# stackclock_base.net
KiCad netlist of a schematic drawn in EAGLE
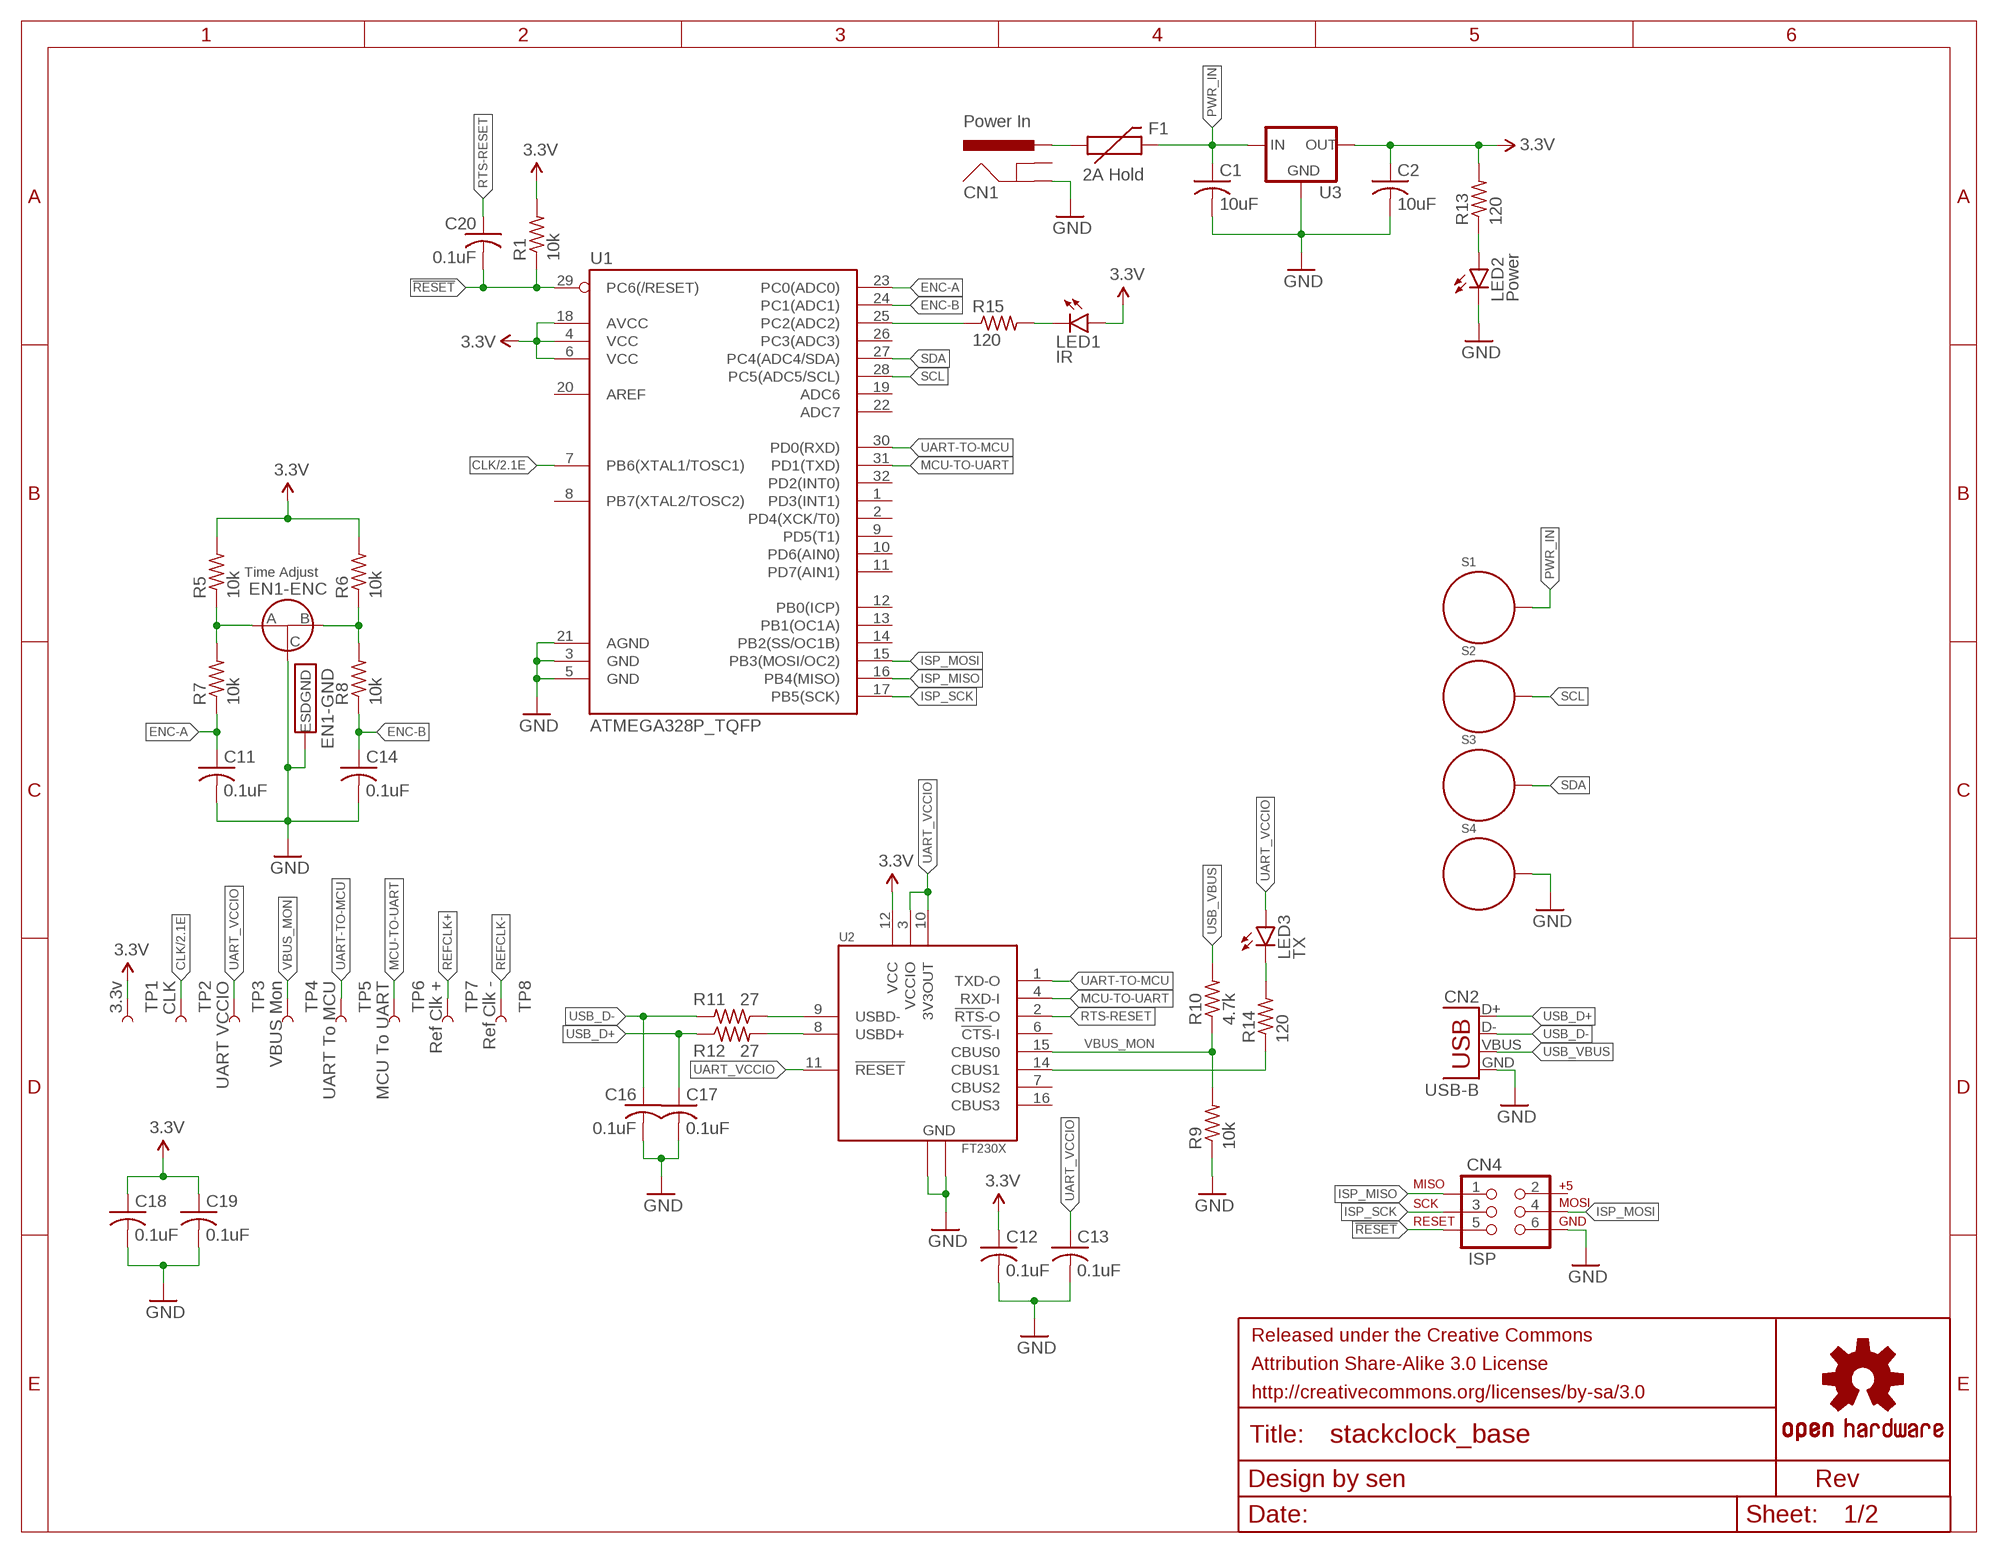
[diagram p0: schematic, sheet 1]
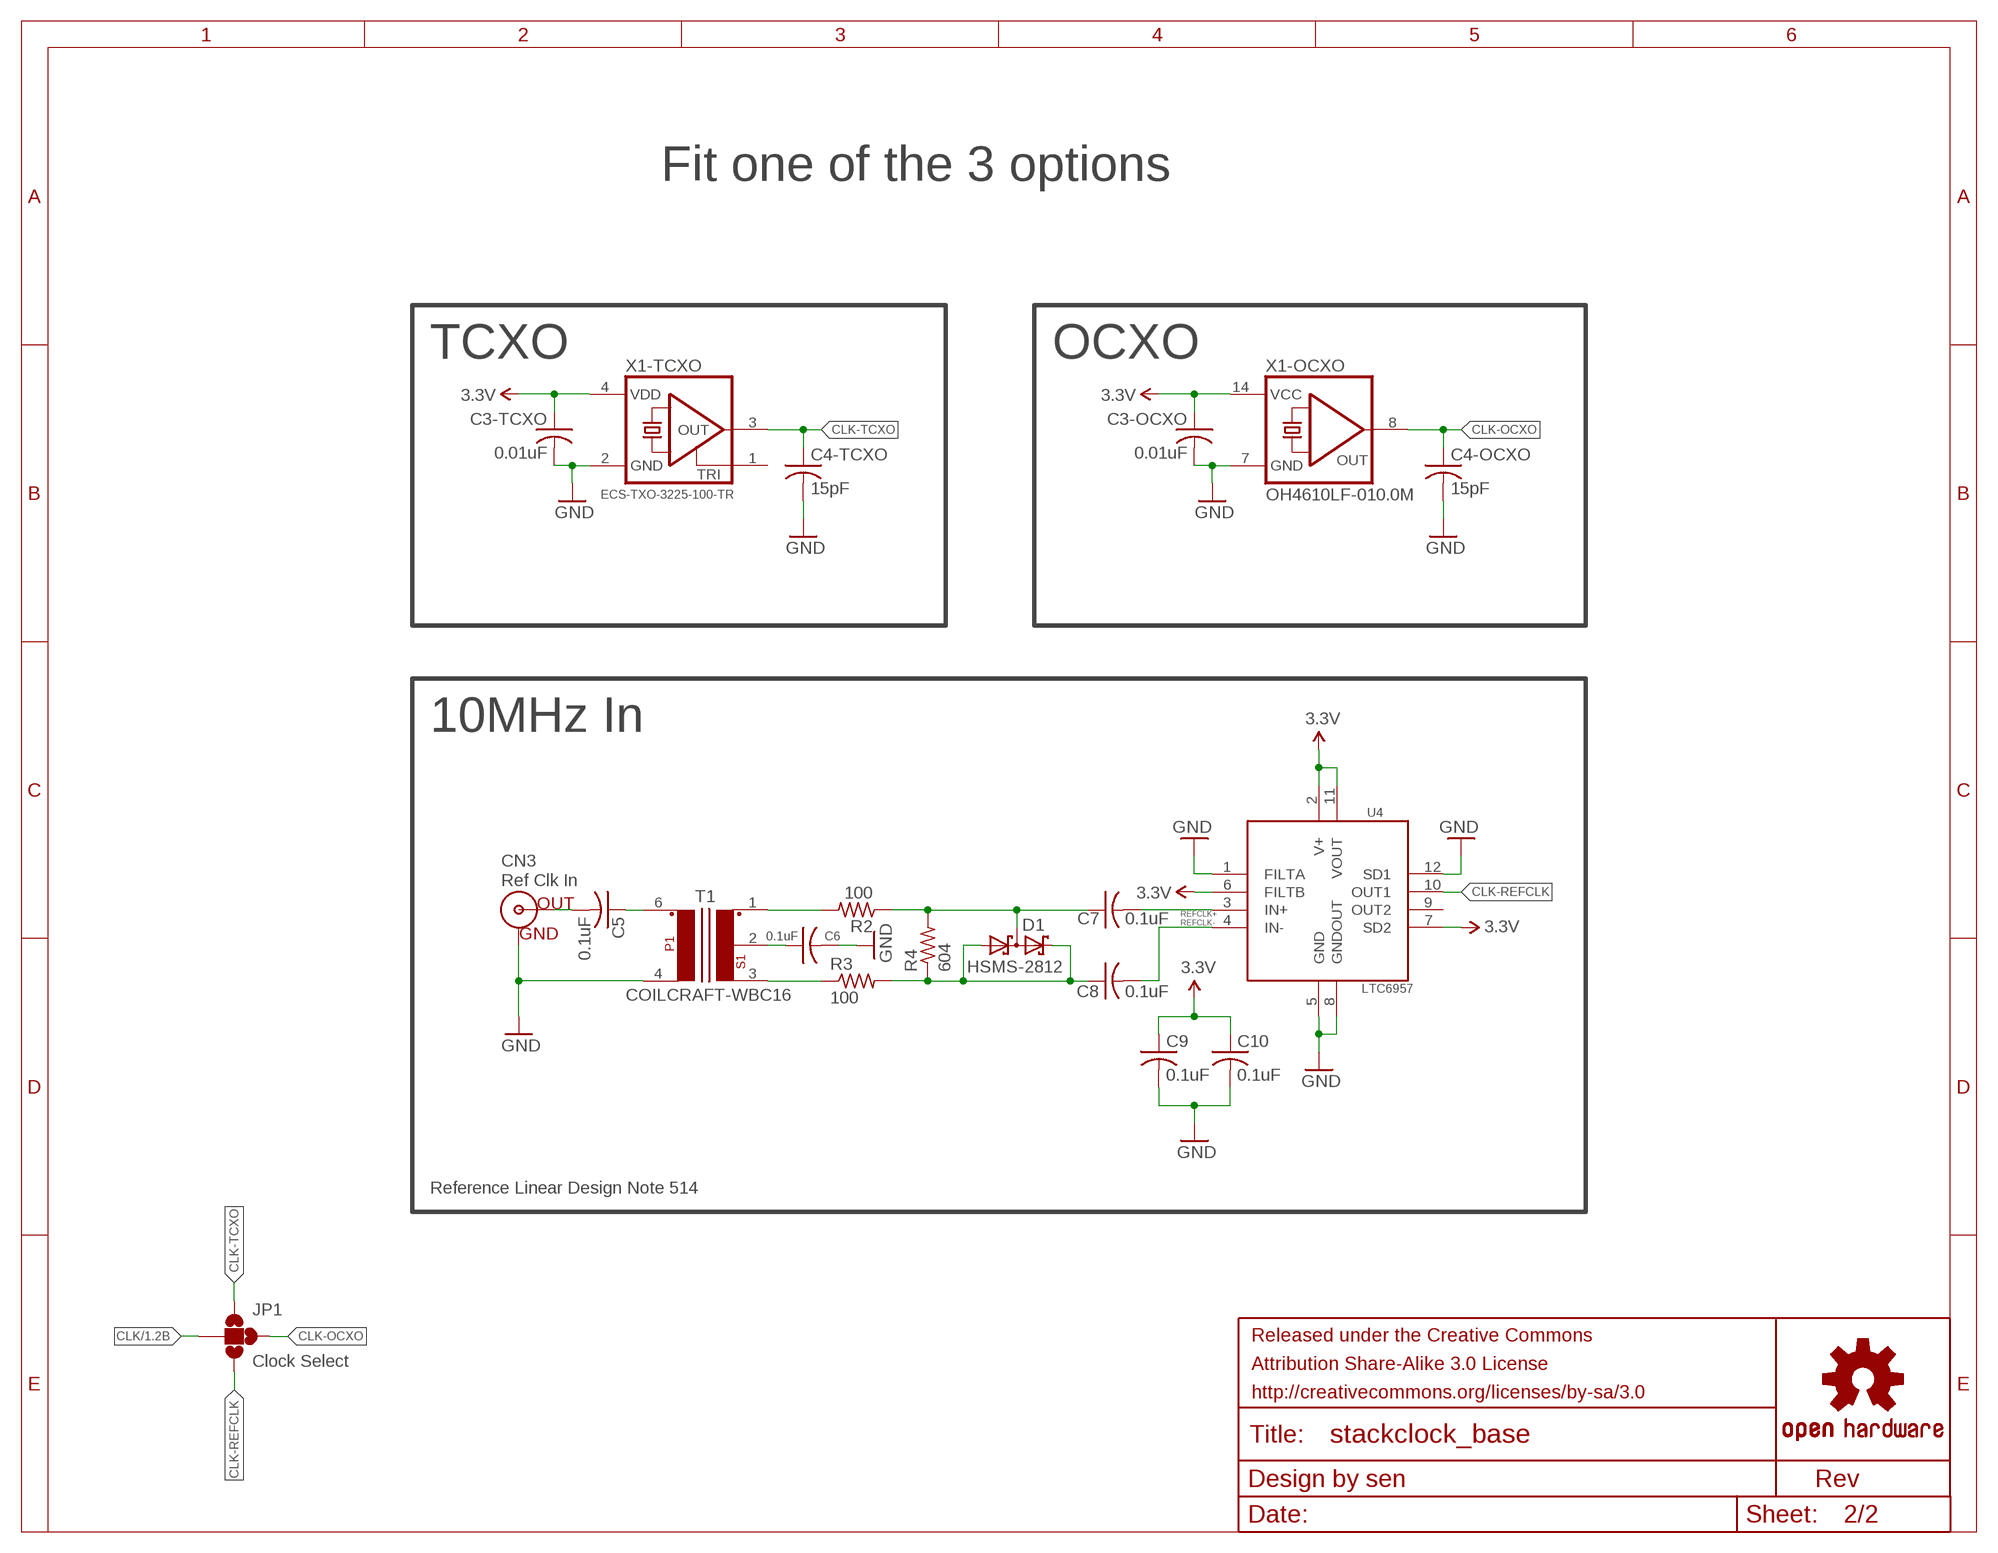
[diagram p1: schematic, sheet 2]

(export (version "E")
  (design (tool "Eeschema 10.0.6"))
  (components
    (comp (ref "C3-OCXO")
      (value "0.01uF")
      (footprint "eagle-import:C0603")
      (libsource (lib "eagle-import") (part "C-USC0603"))
    )
    (comp (ref "C3-TCXO")
      (value "0.01uF")
      (footprint "eagle-import:C0603")
      (libsource (lib "eagle-import") (part "C-USC0603"))
    )
    (comp (ref "C4-OCXO")
      (value "15pF")
      (footprint "eagle-import:C0603")
      (libsource (lib "eagle-import") (part "C-USC0603"))
    )
    (comp (ref "C4-TCXO")
      (value "15pF")
      (footprint "eagle-import:C0603")
      (libsource (lib "eagle-import") (part "C-USC0603"))
    )
    (comp (ref "C5")
      (value "0.1uF")
      (footprint "eagle-import:C0603")
      (libsource (lib "eagle-import") (part "C-USC0603"))
    )
    (comp (ref "C6")
      (value "0.1uF")
      (footprint "eagle-import:C0603")
      (libsource (lib "eagle-import") (part "C-USC0603"))
    )
    (comp (ref "C7")
      (value "0.1uF")
      (footprint "eagle-import:C0603")
      (libsource (lib "eagle-import") (part "C-USC0603"))
    )
    (comp (ref "C8")
      (value "0.1uF")
      (footprint "eagle-import:C0603")
      (libsource (lib "eagle-import") (part "C-USC0603"))
    )
    (comp (ref "C9")
      (value "0.1uF")
      (footprint "eagle-import:C0603")
      (libsource (lib "eagle-import") (part "C-USC0603"))
    )
    (comp (ref "C10")
      (value "0.1uF")
      (footprint "eagle-import:C0603")
      (libsource (lib "eagle-import") (part "C-USC0603"))
    )
    (comp (ref "CN3")
      (value "Ref Clk In")
      (footprint "eagle-import:BNC")
      (libsource (lib "eagle-import") (part "BNCPTH"))
    )
    (comp (ref "D1")
      (value "HSMS-2812")
      (footprint "eagle-import:SOT23")
      (libsource (lib "eagle-import") (part "BAT54S"))
    )
    (comp (ref "FRAME2")
      (value "FRAME-LETTER-GRID-OSHW-SENOSHW-LOGO-L")
      (footprint "eagle-import:OSHW-LOGO-L")
      (fields (field (name "REV") "001"))
      (libsource (lib "eagle-import") (part "FRAME-LETTER-GRID-OSHW-SENOSHW-LOGO-L"))
    )
    (comp (ref "JP1")
      (value "Clock Select")
      (footprint "eagle-import:PAD-JUMPER-4-NO_YES_SILK")
      (libsource (lib "eagle-import") (part "JUMPER-PAD-4-NOYES_SILK"))
    )
    (comp (ref "R2")
      (value "100")
      (footprint "eagle-import:R0603")
      (libsource (lib "eagle-import") (part "R-US_R0603"))
    )
    (comp (ref "R3")
      (value "100")
      (footprint "eagle-import:R0603")
      (libsource (lib "eagle-import") (part "R-US_R0603"))
    )
    (comp (ref "R4")
      (value "604")
      (footprint "eagle-import:R0603")
      (libsource (lib "eagle-import") (part "R-US_R0603"))
    )
    (comp (ref "T1")
      (value "COILCRAFT-WBC16")
      (footprint "eagle-import:COILCRAFT-WBC")
      (libsource (lib "eagle-import") (part "COILCRAFT-WBC16-1TL"))
    )
    (comp (ref "U4")
      (value "LTC6957")
      (footprint "eagle-import:MSOP12")
      (libsource (lib "eagle-import") (part "LTC6957"))
    )
    (comp (ref "X1-OCXO")
      (value "OH4610LF-010.0M")
      (footprint "eagle-import:DIL14S")
      (libsource (lib "eagle-import") (part "QG5860"))
    )
    (comp (ref "X1-TCXO")
      (value "ECS-TXO-3225-100-TR")
      (footprint "eagle-import:ASE")
      (libsource (lib "eagle-import") (part "ASE"))
    )
    (comp (ref "C1")
      (value "10uF")
      (footprint "eagle-import:C0805")
      (libsource (lib "eagle-import") (part "C-USC0805"))
    )
    (comp (ref "C2")
      (value "10uF")
      (footprint "eagle-import:C0805")
      (libsource (lib "eagle-import") (part "C-USC0805"))
    )
    (comp (ref "C11")
      (value "0.1uF")
      (footprint "eagle-import:C0603")
      (libsource (lib "eagle-import") (part "C-USC0603"))
    )
    (comp (ref "C12")
      (value "0.1uF")
      (footprint "eagle-import:C0603")
      (libsource (lib "eagle-import") (part "C-USC0603"))
    )
    (comp (ref "C13")
      (value "0.1uF")
      (footprint "eagle-import:C0603")
      (libsource (lib "eagle-import") (part "C-USC0603"))
    )
    (comp (ref "C14")
      (value "0.1uF")
      (footprint "eagle-import:C0603")
      (libsource (lib "eagle-import") (part "C-USC0603"))
    )
    (comp (ref "C16")
      (value "0.1uF")
      (footprint "eagle-import:C0603")
      (libsource (lib "eagle-import") (part "C-USC0603"))
    )
    (comp (ref "C17")
      (value "0.1uF")
      (footprint "eagle-import:C0603")
      (libsource (lib "eagle-import") (part "C-USC0603"))
    )
    (comp (ref "C18")
      (value "0.1uF")
      (footprint "eagle-import:C0603")
      (libsource (lib "eagle-import") (part "C-USC0603"))
    )
    (comp (ref "C19")
      (value "0.1uF")
      (footprint "eagle-import:C0603")
      (libsource (lib "eagle-import") (part "C-USC0603"))
    )
    (comp (ref "C20")
      (value "0.1uF")
      (footprint "eagle-import:C0603")
      (libsource (lib "eagle-import") (part "C-USC0603"))
    )
    (comp (ref "CN1")
      (value "Power In")
      (footprint "eagle-import:POWER_JACK_PTH")
      (libsource (lib "eagle-import") (part "POWER_JACKPTH"))
    )
    (comp (ref "CN2")
      (value "USB-B")
      (footprint "eagle-import:USB-B-PTH")
      (libsource (lib "eagle-import") (part "USBPTH"))
    )
    (comp (ref "CN4")
      (value "ISP")
      (footprint "eagle-import:2X3_LOCK")
      (libsource (lib "eagle-import") (part "AVR_SPI_PRG_62X3_LOCK"))
    )
    (comp (ref "EN1")
      (value "Time Adjust")
      (footprint "eagle-import:BOURNS-PEC12R-2XXXF-N")
      (libsource (lib "eagle-import") (part "BOURNS-PEC12R-2XXXF-N"))
    )
    (comp (ref "F1")
      (value "2A Hold")
      (footprint "eagle-import:PTC-1206")
      (libsource (lib "eagle-import") (part "PTCSMD"))
    )
    (comp (ref "FRAME1")
      (value "FRAME-LETTER-GRID-OSHW-SENOSHW-LOGO-L")
      (footprint "eagle-import:OSHW-LOGO-L")
      (fields (field (name "REV") "001"))
      (libsource (lib "eagle-import") (part "FRAME-LETTER-GRID-OSHW-SENOSHW-LOGO-L"))
    )
    (comp (ref "LED1")
      (value "IR")
      (footprint "eagle-import:LED-1206")
      (libsource (lib "eagle-import") (part "LED1206"))
    )
    (comp (ref "LED2")
      (value "Power")
      (footprint "eagle-import:LED-0603")
      (libsource (lib "eagle-import") (part "LED0603"))
    )
    (comp (ref "LED3")
      (value "TX")
      (footprint "eagle-import:LED-0603")
      (libsource (lib "eagle-import") (part "LED0603"))
    )
    (comp (ref "R1")
      (value "10k")
      (footprint "eagle-import:R0603")
      (libsource (lib "eagle-import") (part "R-US_R0603"))
    )
    (comp (ref "R5")
      (value "10k")
      (footprint "eagle-import:R0603")
      (libsource (lib "eagle-import") (part "R-US_R0603"))
    )
    (comp (ref "R6")
      (value "10k")
      (footprint "eagle-import:R0603")
      (libsource (lib "eagle-import") (part "R-US_R0603"))
    )
    (comp (ref "R7")
      (value "10k")
      (footprint "eagle-import:R0603")
      (libsource (lib "eagle-import") (part "R-US_R0603"))
    )
    (comp (ref "R8")
      (value "10k")
      (footprint "eagle-import:R0603")
      (libsource (lib "eagle-import") (part "R-US_R0603"))
    )
    (comp (ref "R9")
      (value "10k")
      (footprint "eagle-import:R0603")
      (libsource (lib "eagle-import") (part "R-US_R0603"))
    )
    (comp (ref "R10")
      (value "4.7k")
      (footprint "eagle-import:R0603")
      (libsource (lib "eagle-import") (part "R-US_R0603"))
    )
    (comp (ref "R11")
      (value "27")
      (footprint "eagle-import:R0603")
      (libsource (lib "eagle-import") (part "R-US_R0603"))
    )
    (comp (ref "R12")
      (value "27")
      (footprint "eagle-import:R0603")
      (libsource (lib "eagle-import") (part "R-US_R0603"))
    )
    (comp (ref "R13")
      (value "120")
      (footprint "eagle-import:R0603")
      (libsource (lib "eagle-import") (part "R-US_R0603"))
    )
    (comp (ref "R14")
      (value "120")
      (footprint "eagle-import:R0603")
      (libsource (lib "eagle-import") (part "R-US_R0603"))
    )
    (comp (ref "R15")
      (value "120")
      (footprint "eagle-import:R0603")
      (libsource (lib "eagle-import") (part "R-US_R0603"))
    )
    (comp (ref "S1")
      (value "VIN")
      (footprint "eagle-import:STANDOFF-ELECTRICAL")
      (libsource (lib "eagle-import") (part "STANDOFF_ELECTRICAL"))
    )
    (comp (ref "S2")
      (value "SCL")
      (footprint "eagle-import:STANDOFF-ELECTRICAL")
      (libsource (lib "eagle-import") (part "STANDOFF_ELECTRICAL"))
    )
    (comp (ref "S3")
      (value "SDA")
      (footprint "eagle-import:STANDOFF-ELECTRICAL")
      (libsource (lib "eagle-import") (part "STANDOFF_ELECTRICAL"))
    )
    (comp (ref "S4")
      (value "GND")
      (footprint "eagle-import:STANDOFF-ELECTRICAL")
      (libsource (lib "eagle-import") (part "STANDOFF_ELECTRICAL"))
    )
    (comp (ref "TP1")
      (value "3.3v")
      (footprint "eagle-import:TP_15TH")
      (libsource (lib "eagle-import") (part "TEST-POINTTP_15TH_THRU"))
    )
    (comp (ref "TP2")
      (value "CLK")
      (footprint "eagle-import:TP_15TH")
      (libsource (lib "eagle-import") (part "TEST-POINTTP_15TH_THRU"))
    )
    (comp (ref "TP3")
      (value "UART VCCIO")
      (footprint "eagle-import:TP_15TH")
      (libsource (lib "eagle-import") (part "TEST-POINTTP_15TH_THRU"))
    )
    (comp (ref "TP4")
      (value "VBUS Mon")
      (footprint "eagle-import:TP_15TH")
      (libsource (lib "eagle-import") (part "TEST-POINTTP_15TH_THRU"))
    )
    (comp (ref "TP5")
      (value "UART To MCU")
      (footprint "eagle-import:TP_15TH")
      (libsource (lib "eagle-import") (part "TEST-POINTTP_15TH_THRU"))
    )
    (comp (ref "TP6")
      (value "MCU To UART")
      (footprint "eagle-import:TP_15TH")
      (libsource (lib "eagle-import") (part "TEST-POINTTP_15TH_THRU"))
    )
    (comp (ref "TP7")
      (value "Ref Clk +")
      (footprint "eagle-import:TP_15TH")
      (libsource (lib "eagle-import") (part "TEST-POINTTP_15TH_THRU"))
    )
    (comp (ref "TP8")
      (value "Ref Clk -")
      (footprint "eagle-import:TP_15TH")
      (libsource (lib "eagle-import") (part "TEST-POINTTP_15TH_THRU"))
    )
    (comp (ref "U1")
      (value "ATMEGA328P_TQFP")
      (footprint "eagle-import:TQFP32-08")
      (libsource (lib "eagle-import") (part "ATMEGA328P_TQFP"))
    )
    (comp (ref "U2")
      (value "FT230X")
      (footprint "eagle-import:SSOP16")
      (libsource (lib "eagle-import") (part "FT230X"))
    )
    (comp (ref "U3")
      (value "NCP1117DT33G")
      (footprint "eagle-import:DPAK")
      (libsource (lib "eagle-import") (part "V_REG_MC33269DT"))
    )
  )
  (nets
    (net (code "1") (name "3.3V") (class "Default")
      (node (ref "C10") (pin "1") (pinfunction "1_1") (pintype "passive"))
      (node (ref "C12") (pin "1") (pinfunction "1_1") (pintype "passive"))
      (node (ref "C18") (pin "1") (pinfunction "1_1") (pintype "passive"))
      (node (ref "C19") (pin "1") (pinfunction "1_1") (pintype "passive"))
      (node (ref "C2") (pin "1") (pinfunction "1_1") (pintype "passive"))
      (node (ref "C3-OCXO") (pin "1") (pinfunction "1_1") (pintype "passive"))
      (node (ref "C3-TCXO") (pin "1") (pinfunction "1_1") (pintype "passive"))
      (node (ref "C9") (pin "1") (pinfunction "1_1") (pintype "passive"))
      (node (ref "LED1") (pin "A") (pinfunction "A_A") (pintype "passive"))
      (node (ref "R1") (pin "2") (pinfunction "2_2") (pintype "passive"))
      (node (ref "R13") (pin "2") (pinfunction "2_2") (pintype "passive"))
      (node (ref "R5") (pin "2") (pinfunction "2_2") (pintype "passive"))
      (node (ref "R6") (pin "2") (pinfunction "2_2") (pintype "passive"))
      (node (ref "TP1") (pin "P$1") (pinfunction "1_P$1") (pintype "bidirectional"))
      (node (ref "U1") (pin "18") (pinfunction "AVCC_18") (pintype "bidirectional"))
      (node (ref "U1") (pin "4") (pinfunction "VCC_4") (pintype "bidirectional"))
      (node (ref "U1") (pin "6") (pinfunction "VCC_6") (pintype "bidirectional"))
      (node (ref "U2") (pin "12") (pinfunction "VCC_12") (pintype "power_in"))
      (node (ref "U3") (pin "4") (pinfunction "OUT_4") (pintype "passive"))
      (node (ref "U4") (pin "11") (pinfunction "VOUT_11") (pintype "power_in"))
      (node (ref "U4") (pin "2") (pinfunction "V+_2") (pintype "power_in"))
      (node (ref "U4") (pin "6") (pinfunction "FILTB_6") (pintype "input"))
      (node (ref "U4") (pin "7") (pinfunction "SD2_7") (pintype "input"))
      (node (ref "X1-OCXO") (pin "14") (pinfunction "VCC_14") (pintype "power_in"))
      (node (ref "X1-TCXO") (pin "4") (pinfunction "VDD_4") (pintype "power_in"))
    )
    (net (code "2") (name "CLK") (class "Default")
      (node (ref "JP1") (pin "C") (pinfunction "C_C") (pintype "passive"))
      (node (ref "TP2") (pin "P$1") (pinfunction "1_P$1") (pintype "bidirectional"))
      (node (ref "U1") (pin "7") (pinfunction "PB6(XTAL1/TOSC1)_7") (pintype "bidirectional"))
    )
    (net (code "3") (name "CLK-OCXO") (class "Default")
      (node (ref "C4-OCXO") (pin "1") (pinfunction "1_1") (pintype "passive"))
      (node (ref "JP1") (pin "3") (pinfunction "3_3") (pintype "passive"))
      (node (ref "X1-OCXO") (pin "8") (pinfunction "OUT_8") (pintype "output"))
    )
    (net (code "4") (name "CLK-REFCLK") (class "Default")
      (node (ref "JP1") (pin "2") (pinfunction "2_2") (pintype "passive"))
      (node (ref "U4") (pin "10") (pinfunction "OUT1_10") (pintype "output"))
    )
    (net (code "5") (name "CLK-TCXO") (class "Default")
      (node (ref "C4-TCXO") (pin "1") (pinfunction "1_1") (pintype "passive"))
      (node (ref "JP1") (pin "1") (pinfunction "1_1") (pintype "passive"))
      (node (ref "X1-TCXO") (pin "3") (pinfunction "OUT_3") (pintype "output"))
    )
    (net (code "6") (name "ENC-A") (class "Default")
      (node (ref "C11") (pin "1") (pinfunction "1_1") (pintype "passive"))
      (node (ref "R7") (pin "1") (pinfunction "1_1") (pintype "passive"))
      (node (ref "U1") (pin "23") (pinfunction "PC0(ADC0)_23") (pintype "bidirectional"))
    )
    (net (code "7") (name "ENC-B") (class "Default")
      (node (ref "C14") (pin "1") (pinfunction "1_1") (pintype "passive"))
      (node (ref "R8") (pin "1") (pinfunction "1_1") (pintype "passive"))
      (node (ref "U1") (pin "24") (pinfunction "PC1(ADC1)_24") (pintype "bidirectional"))
    )
    (net (code "8") (name "GND") (class "Default")
      (node (ref "C1") (pin "2") (pinfunction "2_2") (pintype "passive"))
      (node (ref "C10") (pin "2") (pinfunction "2_2") (pintype "passive"))
      (node (ref "C11") (pin "2") (pinfunction "2_2") (pintype "passive"))
      (node (ref "C12") (pin "2") (pinfunction "2_2") (pintype "passive"))
      (node (ref "C13") (pin "2") (pinfunction "2_2") (pintype "passive"))
      (node (ref "C14") (pin "2") (pinfunction "2_2") (pintype "passive"))
      (node (ref "C16") (pin "2") (pinfunction "2_2") (pintype "passive"))
      (node (ref "C17") (pin "2") (pinfunction "2_2") (pintype "passive"))
      (node (ref "C18") (pin "2") (pinfunction "2_2") (pintype "passive"))
      (node (ref "C19") (pin "2") (pinfunction "2_2") (pintype "passive"))
      (node (ref "C2") (pin "2") (pinfunction "2_2") (pintype "passive"))
      (node (ref "C3-OCXO") (pin "2") (pinfunction "2_2") (pintype "passive"))
      (node (ref "C3-TCXO") (pin "2") (pinfunction "2_2") (pintype "passive"))
      (node (ref "C4-OCXO") (pin "2") (pinfunction "2_2") (pintype "passive"))
      (node (ref "C4-TCXO") (pin "2") (pinfunction "2_2") (pintype "passive"))
      (node (ref "C6") (pin "2") (pinfunction "2_2") (pintype "passive"))
      (node (ref "C9") (pin "2") (pinfunction "2_2") (pintype "passive"))
      (node (ref "CN1") (pin "GND") (pinfunction "GND_GND") (pintype "bidirectional"))
      (node (ref "CN2") (pin "GND") (pinfunction "GND_GND") (pintype "bidirectional"))
      (node (ref "CN3") (pin "GND") (pinfunction "GND_GND") (pintype "bidirectional"))
      (node (ref "CN4") (pin "6") (pinfunction "6_6") (pintype "passive"))
      (node (ref "EN1") (pin "C") (pinfunction "C_C") (pintype "passive"))
      (node (ref "EN1") (pin "SUPPORT1") (pinfunction "ESDGND_SUPPORT1") (pintype "passive"))
      (node (ref "EN1") (pin "SUPPORT2") (pinfunction "ESDGND_SUPPORT2") (pintype "passive"))
      (node (ref "LED2") (pin "C") (pinfunction "C_C") (pintype "passive"))
      (node (ref "R9") (pin "1") (pinfunction "1_1") (pintype "passive"))
      (node (ref "S4") (pin "P1") (pinfunction "P$1_P1") (pintype "bidirectional"))
      (node (ref "T1") (pin "4") (pinfunction "PRI-2_4") (pintype "passive"))
      (node (ref "U1") (pin "21") (pinfunction "AGND_21") (pintype "bidirectional"))
      (node (ref "U1") (pin "3") (pinfunction "GND_3") (pintype "bidirectional"))
      (node (ref "U1") (pin "5") (pinfunction "GND_5") (pintype "bidirectional"))
      (node (ref "U2") (pin "13") (pinfunction "GND_13") (pintype "power_in"))
      (node (ref "U2") (pin "5") (pinfunction "GND_5") (pintype "power_in"))
      (node (ref "U3") (pin "1") (pinfunction "GND_1") (pintype "input"))
      (node (ref "U4") (pin "1") (pinfunction "FILTA_1") (pintype "input"))
      (node (ref "U4") (pin "12") (pinfunction "SD1_12") (pintype "input"))
      (node (ref "U4") (pin "5") (pinfunction "GND_5") (pintype "power_in"))
      (node (ref "U4") (pin "8") (pinfunction "GNDOUT_8") (pintype "power_in"))
      (node (ref "X1-OCXO") (pin "7") (pinfunction "GND_7") (pintype "power_in"))
      (node (ref "X1-TCXO") (pin "2") (pinfunction "GND_2") (pintype "power_in"))
    )
    (net (code "9") (name "ISP_MISO") (class "Default")
      (node (ref "CN4") (pin "1") (pinfunction "1_1") (pintype "passive"))
      (node (ref "U1") (pin "16") (pinfunction "PB4(MISO)_16") (pintype "bidirectional"))
    )
    (net (code "10") (name "ISP_MOSI") (class "Default")
      (node (ref "CN4") (pin "4") (pinfunction "4_4") (pintype "passive"))
      (node (ref "U1") (pin "15") (pinfunction "PB3(MOSI/OC2)_15") (pintype "bidirectional"))
    )
    (net (code "11") (name "ISP_SCK") (class "Default")
      (node (ref "CN4") (pin "3") (pinfunction "3_3") (pintype "passive"))
      (node (ref "U1") (pin "17") (pinfunction "PB5(SCK)_17") (pintype "bidirectional"))
    )
    (net (code "12") (name "MCU-TO-UART") (class "Default")
      (node (ref "TP6") (pin "P$1") (pinfunction "1_P$1") (pintype "bidirectional"))
      (node (ref "U1") (pin "31") (pinfunction "PD1(TXD)_31") (pintype "bidirectional"))
      (node (ref "U2") (pin "4") (pinfunction "RXD-I_4") (pintype "input"))
    )
    (net (code "13") (name "Net-(CN1-PadPWR)") (class "Default")
      (node (ref "CN1") (pin "PWR") (pinfunction "PWR_PWR") (pintype "bidirectional"))
      (node (ref "F1") (pin "1") (pinfunction "1_1") (pintype "bidirectional"))
    )
    (net (code "14") (name "Net-(CN3-OUT)") (class "Default")
      (node (ref "C5") (pin "2") (pinfunction "2_2") (pintype "passive"))
      (node (ref "CN3") (pin "S") (pinfunction "OUT_S") (pintype "bidirectional"))
    )
    (net (code "15") (name "Net-(D1-A1)") (class "Default")
      (node (ref "C8") (pin "1") (pinfunction "1_1") (pintype "passive"))
      (node (ref "D1") (pin "1") (pinfunction "A1_1") (pintype "passive"))
      (node (ref "D1") (pin "2") (pinfunction "C2_2") (pintype "passive"))
      (node (ref "R3") (pin "2") (pinfunction "2_2") (pintype "passive"))
      (node (ref "R4") (pin "1") (pinfunction "1_1") (pintype "passive"))
    )
    (net (code "16") (name "Net-(D1-C1A2)") (class "Default")
      (node (ref "C7") (pin "1") (pinfunction "1_1") (pintype "passive"))
      (node (ref "D1") (pin "3") (pinfunction "C1A2_3") (pintype "passive"))
      (node (ref "R2") (pin "1") (pinfunction "1_1") (pintype "passive"))
      (node (ref "R4") (pin "2") (pinfunction "2_2") (pintype "passive"))
    )
    (net (code "17") (name "Net-(EN1-PadA)") (class "Default")
      (node (ref "EN1") (pin "A") (pinfunction "A_A") (pintype "passive"))
      (node (ref "R5") (pin "1") (pinfunction "1_1") (pintype "passive"))
      (node (ref "R7") (pin "2") (pinfunction "2_2") (pintype "passive"))
    )
    (net (code "18") (name "Net-(EN1-PadB)") (class "Default")
      (node (ref "EN1") (pin "B") (pinfunction "B_B") (pintype "passive"))
      (node (ref "R6") (pin "1") (pinfunction "1_1") (pintype "passive"))
      (node (ref "R8") (pin "2") (pinfunction "2_2") (pintype "passive"))
    )
    (net (code "19") (name "Net-(LED1-PadC)") (class "Default")
      (node (ref "LED1") (pin "C") (pinfunction "C_C") (pintype "passive"))
      (node (ref "R15") (pin "2") (pinfunction "2_2") (pintype "passive"))
    )
    (net (code "20") (name "Net-(LED2-PadA)") (class "Default")
      (node (ref "LED2") (pin "A") (pinfunction "A_A") (pintype "passive"))
      (node (ref "R13") (pin "1") (pinfunction "1_1") (pintype "passive"))
    )
    (net (code "21") (name "Net-(LED3-PadC)") (class "Default")
      (node (ref "LED3") (pin "C") (pinfunction "C_C") (pintype "passive"))
      (node (ref "R14") (pin "2") (pinfunction "2_2") (pintype "passive"))
    )
    (net (code "22") (name "Net-(T1-PRI-1)") (class "Default")
      (node (ref "C5") (pin "1") (pinfunction "1_1") (pintype "passive"))
      (node (ref "T1") (pin "6") (pinfunction "PRI-1_6") (pintype "passive"))
    )
    (net (code "23") (name "Net-(T1-SEC-1)") (class "Default")
      (node (ref "R2") (pin "2") (pinfunction "2_2") (pintype "passive"))
      (node (ref "T1") (pin "1") (pinfunction "SEC-1_1") (pintype "passive"))
    )
    (net (code "24") (name "Net-(T1-SEC-2)") (class "Default")
      (node (ref "R3") (pin "1") (pinfunction "1_1") (pintype "passive"))
      (node (ref "T1") (pin "3") (pinfunction "SEC-2_3") (pintype "passive"))
    )
    (net (code "25") (name "Net-(T1-SEC-CT)") (class "Default")
      (node (ref "C6") (pin "1") (pinfunction "1_1") (pintype "passive"))
      (node (ref "T1") (pin "2") (pinfunction "SEC-CT_2") (pintype "passive"))
    )
    (net (code "26") (name "Net-(U1-PC2(ADC2))") (class "Default")
      (node (ref "R15") (pin "1") (pinfunction "1_1") (pintype "passive"))
      (node (ref "U1") (pin "25") (pinfunction "PC2(ADC2)_25") (pintype "bidirectional"))
    )
    (net (code "27") (name "Net-(U2-CBUS1)") (class "Default")
      (node (ref "R14") (pin "1") (pinfunction "1_1") (pintype "passive"))
      (node (ref "U2") (pin "14") (pinfunction "CBUS1_14") (pintype "bidirectional"))
    )
    (net (code "28") (name "Net-(U2-USBD+)") (class "Default")
      (node (ref "R12") (pin "2") (pinfunction "2_2") (pintype "passive"))
      (node (ref "U2") (pin "8") (pinfunction "USBD+_8") (pintype "bidirectional"))
    )
    (net (code "29") (name "Net-(U2-USBD-)") (class "Default")
      (node (ref "R11") (pin "1") (pinfunction "1_1") (pintype "passive"))
      (node (ref "U2") (pin "9") (pinfunction "USBD-_9") (pintype "bidirectional"))
    )
    (net (code "30") (name "PWR_IN") (class "Default")
      (node (ref "C1") (pin "1") (pinfunction "1_1") (pintype "passive"))
      (node (ref "F1") (pin "2") (pinfunction "2_2") (pintype "bidirectional"))
      (node (ref "S1") (pin "P1") (pinfunction "P$1_P1") (pintype "bidirectional"))
      (node (ref "U3") (pin "3") (pinfunction "IN_3") (pintype "input"))
    )
    (net (code "31") (name "REFCLK+") (class "Default")
      (node (ref "C7") (pin "2") (pinfunction "2_2") (pintype "passive"))
      (node (ref "TP7") (pin "P$1") (pinfunction "1_P$1") (pintype "bidirectional"))
      (node (ref "U4") (pin "3") (pinfunction "IN+_3") (pintype "input"))
    )
    (net (code "32") (name "REFCLK-") (class "Default")
      (node (ref "C8") (pin "2") (pinfunction "2_2") (pintype "passive"))
      (node (ref "TP8") (pin "P$1") (pinfunction "1_P$1") (pintype "bidirectional"))
      (node (ref "U4") (pin "4") (pinfunction "IN-_4") (pintype "input"))
    )
    (net (code "33") (name "RTS-RESET") (class "Default")
      (node (ref "C20") (pin "1") (pinfunction "1_1") (pintype "passive"))
      (node (ref "U2") (pin "2") (pinfunction "~{RTS}-O_2") (pintype "output"))
    )
    (net (code "34") (name "SCL") (class "Default")
      (node (ref "S2") (pin "P1") (pinfunction "P$1_P1") (pintype "bidirectional"))
      (node (ref "U1") (pin "28") (pinfunction "PC5(ADC5/SCL)_28") (pintype "bidirectional"))
    )
    (net (code "35") (name "SDA") (class "Default")
      (node (ref "S3") (pin "P1") (pinfunction "P$1_P1") (pintype "bidirectional"))
      (node (ref "U1") (pin "27") (pinfunction "PC4(ADC4/SDA)_27") (pintype "bidirectional"))
    )
    (net (code "36") (name "UART-TO-MCU") (class "Default")
      (node (ref "TP5") (pin "P$1") (pinfunction "1_P$1") (pintype "bidirectional"))
      (node (ref "U1") (pin "30") (pinfunction "PD0(RXD)_30") (pintype "bidirectional"))
      (node (ref "U2") (pin "1") (pinfunction "TXD-O_1") (pintype "output"))
    )
    (net (code "37") (name "UART_VCCIO") (class "Default")
      (node (ref "C13") (pin "1") (pinfunction "1_1") (pintype "passive"))
      (node (ref "LED3") (pin "A") (pinfunction "A_A") (pintype "passive"))
      (node (ref "TP3") (pin "P$1") (pinfunction "1_P$1") (pintype "bidirectional"))
      (node (ref "U2") (pin "10") (pinfunction "3V3OUT_10") (pintype "power_in"))
      (node (ref "U2") (pin "11") (pinfunction "~{RESET}_11") (pintype "input"))
      (node (ref "U2") (pin "3") (pinfunction "VCCIO_3") (pintype "power_in"))
    )
    (net (code "38") (name "USB_D+") (class "Default")
      (node (ref "C17") (pin "1") (pinfunction "1_1") (pintype "passive"))
      (node (ref "CN2") (pin "D+") (pinfunction "D+_D+") (pintype "bidirectional"))
      (node (ref "R12") (pin "1") (pinfunction "1_1") (pintype "passive"))
    )
    (net (code "39") (name "USB_D-") (class "Default")
      (node (ref "C16") (pin "1") (pinfunction "1_1") (pintype "passive"))
      (node (ref "CN2") (pin "D-") (pinfunction "D-_D-") (pintype "bidirectional"))
      (node (ref "R11") (pin "2") (pinfunction "2_2") (pintype "passive"))
    )
    (net (code "40") (name "USB_VBUS") (class "Default")
      (node (ref "CN2") (pin "VBUS") (pinfunction "VBUS_VBUS") (pintype "bidirectional"))
      (node (ref "R10") (pin "2") (pinfunction "2_2") (pintype "passive"))
    )
    (net (code "41") (name "VBUS_MON") (class "Default")
      (node (ref "R10") (pin "1") (pinfunction "1_1") (pintype "passive"))
      (node (ref "R9") (pin "2") (pinfunction "2_2") (pintype "passive"))
      (node (ref "TP4") (pin "P$1") (pinfunction "1_P$1") (pintype "bidirectional"))
      (node (ref "U2") (pin "15") (pinfunction "CBUS0_15") (pintype "bidirectional"))
    )
    (net (code "42") (name "unconnected-(CN1-PadGNDBREAK)") (class "Default")
      (node (ref "CN1") (pin "GNDBREAK") (pinfunction "GNDBREAK_GNDBREAK") (pintype "bidirectional"))
    )
    (net (code "43") (name "unconnected-(CN4-Pad2)") (class "Default")
      (node (ref "CN4") (pin "2") (pinfunction "2_2") (pintype "passive"))
    )
    (net (code "44") (name "unconnected-(U1-ADC6-Pad19)") (class "Default")
      (node (ref "U1") (pin "19") (pinfunction "ADC6_19") (pintype "bidirectional"))
    )
    (net (code "45") (name "unconnected-(U1-ADC7-Pad22)") (class "Default")
      (node (ref "U1") (pin "22") (pinfunction "ADC7_22") (pintype "bidirectional"))
    )
    (net (code "46") (name "unconnected-(U1-AREF-Pad20)") (class "Default")
      (node (ref "U1") (pin "20") (pinfunction "AREF_20") (pintype "bidirectional"))
    )
    (net (code "47") (name "unconnected-(U1-PB0(ICP)-Pad12)") (class "Default")
      (node (ref "U1") (pin "12") (pinfunction "PB0(ICP)_12") (pintype "bidirectional"))
    )
    (net (code "48") (name "unconnected-(U1-PB1(OC1A)-Pad13)") (class "Default")
      (node (ref "U1") (pin "13") (pinfunction "PB1(OC1A)_13") (pintype "bidirectional"))
    )
    (net (code "49") (name "unconnected-(U1-PB2(SS{slash}OC1B)-Pad14)") (class "Default")
      (node (ref "U1") (pin "14") (pinfunction "PB2(SS/OC1B)_14") (pintype "bidirectional"))
    )
    (net (code "50") (name "unconnected-(U1-PB7(XTAL2{slash}TOSC2)-Pad8)") (class "Default")
      (node (ref "U1") (pin "8") (pinfunction "PB7(XTAL2/TOSC2)_8") (pintype "bidirectional"))
    )
    (net (code "51") (name "unconnected-(U1-PC3(ADC3)-Pad26)") (class "Default")
      (node (ref "U1") (pin "26") (pinfunction "PC3(ADC3)_26") (pintype "bidirectional"))
    )
    (net (code "52") (name "unconnected-(U1-PD2(INT0)-Pad32)") (class "Default")
      (node (ref "U1") (pin "32") (pinfunction "PD2(INT0)_32") (pintype "bidirectional"))
    )
    (net (code "53") (name "unconnected-(U1-PD3(INT1)-Pad1)") (class "Default")
      (node (ref "U1") (pin "1") (pinfunction "PD3(INT1)_1") (pintype "bidirectional"))
    )
    (net (code "54") (name "unconnected-(U1-PD4(XCK{slash}T0)-Pad2)") (class "Default")
      (node (ref "U1") (pin "2") (pinfunction "PD4(XCK/T0)_2") (pintype "bidirectional"))
    )
    (net (code "55") (name "unconnected-(U1-PD5(T1)-Pad9)") (class "Default")
      (node (ref "U1") (pin "9") (pinfunction "PD5(T1)_9") (pintype "bidirectional"))
    )
    (net (code "56") (name "unconnected-(U1-PD6(AIN0)-Pad10)") (class "Default")
      (node (ref "U1") (pin "10") (pinfunction "PD6(AIN0)_10") (pintype "bidirectional"))
    )
    (net (code "57") (name "unconnected-(U1-PD7(AIN1)-Pad11)") (class "Default")
      (node (ref "U1") (pin "11") (pinfunction "PD7(AIN1)_11") (pintype "bidirectional"))
    )
    (net (code "58") (name "unconnected-(U2-CBUS2-Pad7)") (class "Default")
      (node (ref "U2") (pin "7") (pinfunction "CBUS2_7") (pintype "bidirectional"))
    )
    (net (code "59") (name "unconnected-(U2-CBUS3-Pad16)") (class "Default")
      (node (ref "U2") (pin "16") (pinfunction "CBUS3_16") (pintype "bidirectional"))
    )
    (net (code "60") (name "unconnected-(U2-~{CTS}-I-Pad6)") (class "Default")
      (node (ref "U2") (pin "6") (pinfunction "~{CTS}-I_6") (pintype "input"))
    )
    (net (code "61") (name "unconnected-(U4-OUT2-Pad9)") (class "Default")
      (node (ref "U4") (pin "9") (pinfunction "OUT2_9") (pintype "output"))
    )
    (net (code "62") (name "unconnected-(X1-TCXO-TRI-Pad1)") (class "Default")
      (node (ref "X1-TCXO") (pin "1") (pinfunction "TRI_1") (pintype "input"))
    )
    (net (code "63") (name "~{RESET}") (class "Default")
      (node (ref "C20") (pin "2") (pinfunction "2_2") (pintype "passive"))
      (node (ref "CN4") (pin "5") (pinfunction "5_5") (pintype "passive"))
      (node (ref "R1") (pin "1") (pinfunction "1_1") (pintype "passive"))
      (node (ref "U1") (pin "29") (pinfunction "PC6(/RESET)_29") (pintype "bidirectional"))
    )
  )
)
